# Power.net
KiCad netlist of a schematic drawn in Altium Designer
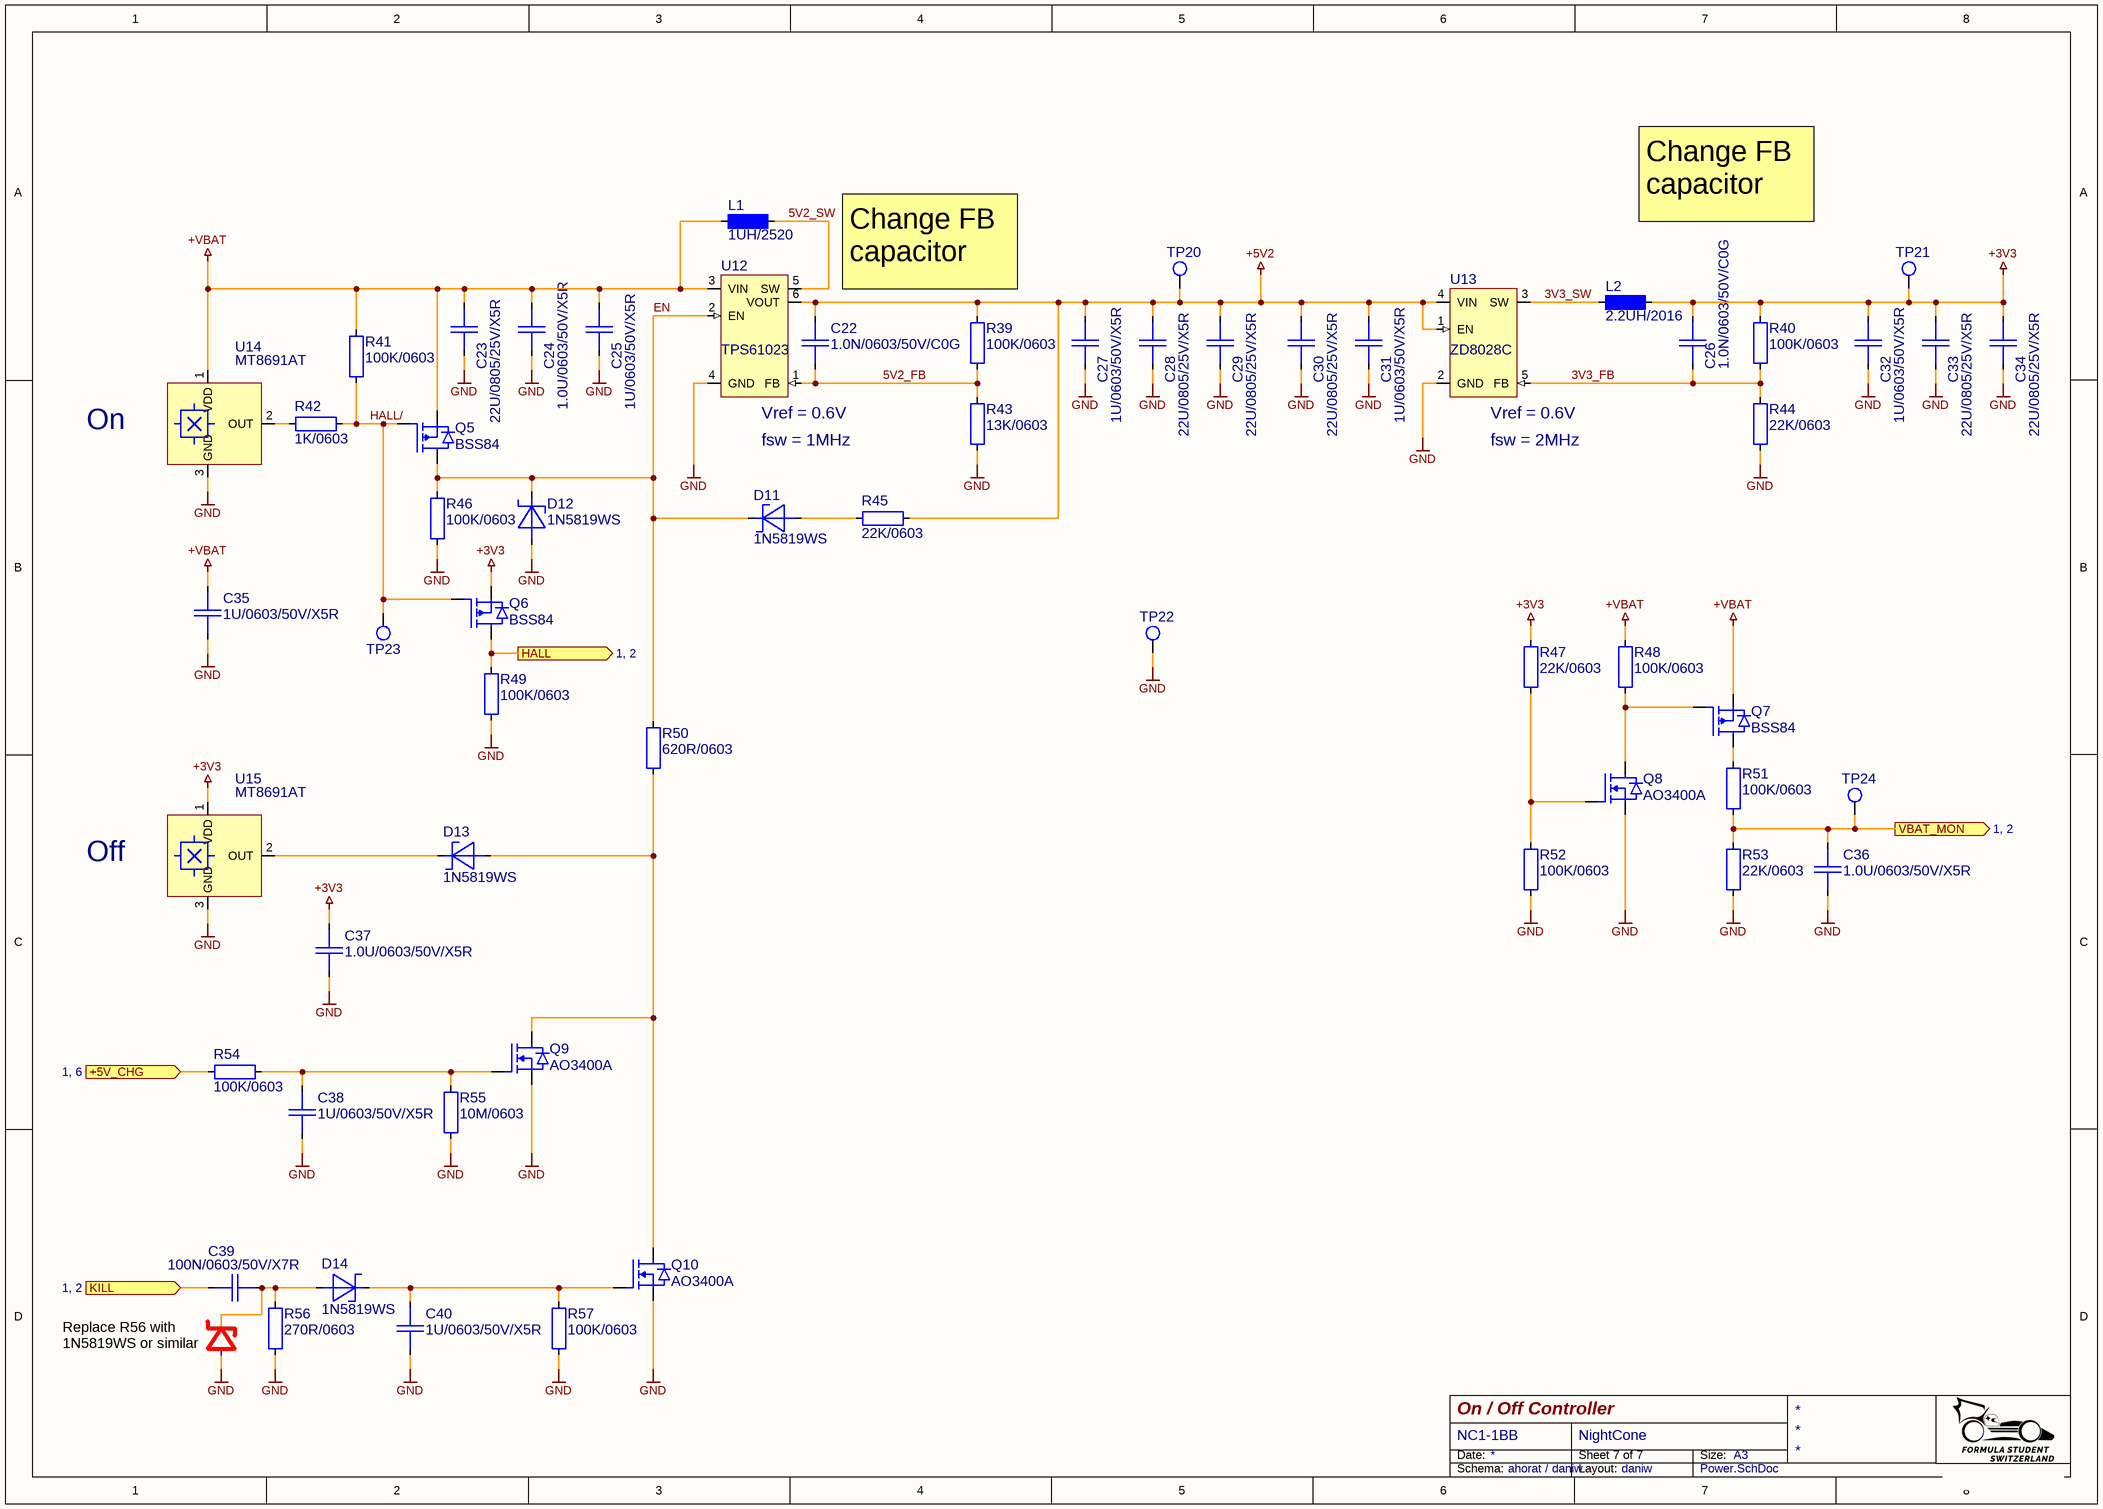
[diagram p0: Power.SchDoc]

(export (version "E")
  (design (tool "Eeschema 10.0.6"))
  (components
    (comp (ref "C22")
      (value "1.0N/0603/50V/C0G")
      (footprint "CAP0603_C0G")
      (description "CAP SM 0603 1.0nF 50V C0G")
      (fields (field (name "MANUFACTURER") "GENERIC"))
      (libsource (lib "daniw_altium_lib") (part "C"))
    )
    (comp (ref "C23")
      (value "22U/0805/25V/X5R")
      (footprint "CAP0805_X7R")
      (description "CAP SM 0805 22uF 25V X5R")
      (fields (field (name "MANUFACTURER") "GENERIC"))
      (libsource (lib "daniw_altium_lib") (part "C"))
    )
    (comp (ref "C24")
      (value "1.0U/0603/50V/X5R")
      (footprint "CAP0603_X7R")
      (description "CAP SM 0603 1.0uF 50V X5R")
      (fields (field (name "MANUFACTURER") "GENERIC"))
      (libsource (lib "daniw_altium_lib") (part "C"))
    )
    (comp (ref "C25")
      (value "1U/0603/50V/X5R")
      (footprint "CAP0603_X7R")
      (description "CAP SM 0603 1.0uF 50V X5R")
      (fields (field (name "MANUFACTURER") "GENERIC"))
      (libsource (lib "daniw_altium_lib") (part "C"))
    )
    (comp (ref "C26")
      (value "1.0N/0603/50V/C0G")
      (footprint "CAP0603_C0G")
      (description "CAP SM 0603 1.0nF 50V C0G")
      (fields (field (name "MANUFACTURER") "GENERIC"))
      (libsource (lib "daniw_altium_lib") (part "C"))
    )
    (comp (ref "C27")
      (value "1U/0603/50V/X5R")
      (footprint "CAP0603_X7R")
      (description "CAP SM 0603 1.0uF 50V X5R")
      (fields (field (name "MANUFACTURER") "GENERIC"))
      (libsource (lib "daniw_altium_lib") (part "C"))
    )
    (comp (ref "C28")
      (value "22U/0805/25V/X5R")
      (footprint "CAP0805_X7R")
      (description "CAP SM 0805 22uF 25V X5R")
      (fields (field (name "MANUFACTURER") "GENERIC"))
      (libsource (lib "daniw_altium_lib") (part "C"))
    )
    (comp (ref "C29")
      (value "22U/0805/25V/X5R")
      (footprint "CAP0805_X7R")
      (description "CAP SM 0805 22uF 25V X5R")
      (fields (field (name "MANUFACTURER") "GENERIC"))
      (libsource (lib "daniw_altium_lib") (part "C"))
    )
    (comp (ref "C30")
      (value "22U/0805/25V/X5R")
      (footprint "CAP0805_X7R")
      (description "CAP SM 0805 22uF 25V X5R")
      (fields (field (name "MANUFACTURER") "GENERIC"))
      (libsource (lib "daniw_altium_lib") (part "C"))
    )
    (comp (ref "C31")
      (value "1U/0603/50V/X5R")
      (footprint "CAP0603_X7R")
      (description "CAP SM 0603 1.0uF 50V X5R")
      (fields (field (name "MANUFACTURER") "GENERIC"))
      (libsource (lib "daniw_altium_lib") (part "C"))
    )
    (comp (ref "C32")
      (value "1U/0603/50V/X5R")
      (footprint "CAP0603_X7R")
      (description "CAP SM 0603 1.0uF 50V X5R")
      (fields (field (name "MANUFACTURER") "GENERIC"))
      (libsource (lib "daniw_altium_lib") (part "C"))
    )
    (comp (ref "C33")
      (value "22U/0805/25V/X5R")
      (footprint "CAP0805_X7R")
      (description "CAP SM 0805 22uF 25V X5R")
      (fields (field (name "MANUFACTURER") "GENERIC"))
      (libsource (lib "daniw_altium_lib") (part "C"))
    )
    (comp (ref "C34")
      (value "22U/0805/25V/X5R")
      (footprint "CAP0805_X7R")
      (description "CAP SM 0805 22uF 25V X5R")
      (fields (field (name "MANUFACTURER") "GENERIC"))
      (libsource (lib "daniw_altium_lib") (part "C"))
    )
    (comp (ref "C35")
      (value "1U/0603/50V/X5R")
      (footprint "CAP0603_X7R")
      (description "CAP SM 0603 1.0uF 50V X5R")
      (fields (field (name "MANUFACTURER") "GENERIC"))
      (libsource (lib "daniw_altium_lib") (part "C"))
    )
    (comp (ref "C36")
      (value "1.0U/0603/50V/X5R")
      (footprint "CAP0603_X7R")
      (description "CAP SM 0603 1.0uF 50V X5R")
      (fields (field (name "MANUFACTURER") "GENERIC"))
      (libsource (lib "daniw_altium_lib") (part "C"))
    )
    (comp (ref "C37")
      (value "1.0U/0603/50V/X5R")
      (footprint "CAP0603_X7R")
      (description "CAP SM 0603 1.0uF 50V X5R")
      (fields (field (name "MANUFACTURER") "GENERIC"))
      (libsource (lib "daniw_altium_lib") (part "C"))
    )
    (comp (ref "C38")
      (value "1U/0603/50V/X5R")
      (footprint "CAP0603_X7R")
      (description "CAP SM 0603 1.0uF 50V X5R")
      (fields (field (name "MANUFACTURER") "GENERIC"))
      (libsource (lib "daniw_altium_lib") (part "C"))
    )
    (comp (ref "C39")
      (value "100N/0603/50V/X7R")
      (footprint "CAP0603_X7R")
      (description "CAP SM 0603 100nF 50V X7R")
      (fields (field (name "MANUFACTURER") "GENERIC"))
      (libsource (lib "daniw_altium_lib") (part "C"))
    )
    (comp (ref "C40")
      (value "1U/0603/50V/X5R")
      (footprint "CAP0603_X7R")
      (description "CAP SM 0603 1.0uF 50V X5R")
      (fields (field (name "MANUFACTURER") "GENERIC"))
      (libsource (lib "daniw_altium_lib") (part "C"))
    )
    (comp (ref "D11")
      (value "1N5819WS")
      (footprint "SOD2513X100")
      (description "40V 600mV@1A 1A SOD-323 Schottky Barrier Diodes (SBD) ROHS")
      (fields (field (name "MANUFACTURER") "GENERIC"))
      (libsource (lib "daniw_altium_lib") (part "D_Schottky"))
    )
    (comp (ref "D12")
      (value "1N5819WS")
      (footprint "SOD2513X100")
      (description "40V 600mV@1A 1A SOD-323 Schottky Barrier Diodes (SBD) ROHS")
      (fields (field (name "MANUFACTURER") "GENERIC"))
      (libsource (lib "daniw_altium_lib") (part "D_Schottky"))
    )
    (comp (ref "D13")
      (value "1N5819WS")
      (footprint "SOD2513X100")
      (description "40V 600mV@1A 1A SOD-323 Schottky Barrier Diodes (SBD) ROHS")
      (fields (field (name "MANUFACTURER") "GENERIC"))
      (libsource (lib "daniw_altium_lib") (part "D_Schottky"))
    )
    (comp (ref "D14")
      (value "1N5819WS")
      (footprint "SOD2513X100")
      (description "40V 600mV@1A 1A SOD-323 Schottky Barrier Diodes (SBD) ROHS")
      (fields (field (name "MANUFACTURER") "GENERIC"))
      (libsource (lib "daniw_altium_lib") (part "D_Schottky"))
    )
    (comp (ref "L1")
      (value "1UH/2520")
      (footprint "INDM2520X10")
      (description "1UH 2520 Shielded Inductor SMD")
      (fields (field (name "MANUFACTURER") "GENERIC"))
      (libsource (lib "daniw_altium_lib") (part "L"))
    )
    (comp (ref "L2")
      (value "2.2UH/2016")
      (footprint "INDM2016X10")
      (description "2.2UH 2016 Shielded Inductor SMD")
      (fields (field (name "MANUFACTURER") "GENERIC"))
      (libsource (lib "daniw_altium_lib") (part "L"))
    )
    (comp (ref "Q5")
      (value "BSS84")
      (footprint "SOT2395P280X125-3-SE")
      (description "50V P-Channel MOSFET")
      (fields (field (name "MANUFACTURER") "GENERIC"))
      (libsource (lib "daniw_altium_lib") (part "MOSFET P_SOT23"))
    )
    (comp (ref "Q6")
      (value "BSS84")
      (footprint "SOT2395P280X125-3-SE")
      (description "50V P-Channel MOSFET")
      (fields (field (name "MANUFACTURER") "GENERIC"))
      (libsource (lib "daniw_altium_lib") (part "MOSFET P_SOT23"))
    )
    (comp (ref "Q7")
      (value "BSS84")
      (footprint "SOT2395P280X125-3-SE")
      (description "50V P-Channel MOSFET")
      (fields (field (name "MANUFACTURER") "GENERIC"))
      (libsource (lib "daniw_altium_lib") (part "MOSFET P_SOT23"))
    )
    (comp (ref "Q8")
      (value "AO3400A")
      (footprint "SOT2395P280X125-3-SE")
      (description "30V N-Channel MOSFET")
      (fields (field (name "MANUFACTURER") "Alpha & Omega Semiconductor"))
      (libsource (lib "daniw_altium_lib") (part "MOSFET N_SOT23"))
    )
    (comp (ref "Q9")
      (value "AO3400A")
      (footprint "SOT2395P280X125-3-SE")
      (description "30V N-Channel MOSFET")
      (fields (field (name "MANUFACTURER") "Alpha & Omega Semiconductor"))
      (libsource (lib "daniw_altium_lib") (part "MOSFET N_SOT23"))
    )
    (comp (ref "Q10")
      (value "AO3400A")
      (footprint "SOT2395P280X125-3-SE")
      (description "30V N-Channel MOSFET")
      (fields (field (name "MANUFACTURER") "Alpha & Omega Semiconductor"))
      (libsource (lib "daniw_altium_lib") (part "MOSFET N_SOT23"))
    )
    (comp (ref "R39")
      (value "100K/0603")
      (footprint "R0603-0.40-WW")
      (description "RES SM 0603 100K")
      (fields (field (name "MANUFACTURER") "GENERIC"))
      (libsource (lib "daniw_altium_lib") (part "R"))
    )
    (comp (ref "R40")
      (value "100K/0603")
      (footprint "R0603-0.40-WW")
      (description "RES SM 0603 100K")
      (fields (field (name "MANUFACTURER") "GENERIC"))
      (libsource (lib "daniw_altium_lib") (part "R"))
    )
    (comp (ref "R41")
      (value "100K/0603")
      (footprint "R0603-0.40-WW")
      (description "RES SM 0603 100K")
      (fields (field (name "MANUFACTURER") "GENERIC"))
      (libsource (lib "daniw_altium_lib") (part "R"))
    )
    (comp (ref "R42")
      (value "1K/0603")
      (footprint "R0603-0.40-WW")
      (description "RES SM 0603 1K")
      (fields (field (name "MANUFACTURER") "GENERIC"))
      (libsource (lib "daniw_altium_lib") (part "R"))
    )
    (comp (ref "R43")
      (value "13K/0603")
      (footprint "R0603-0.40-WW")
      (description "RES SM 0603 13K")
      (fields (field (name "MANUFACTURER") "GENERIC"))
      (libsource (lib "daniw_altium_lib") (part "R"))
    )
    (comp (ref "R44")
      (value "22K/0603")
      (footprint "R0603-0.40-WW")
      (description "RES SM 0603 22K")
      (fields (field (name "MANUFACTURER") "GENERIC"))
      (libsource (lib "daniw_altium_lib") (part "R"))
    )
    (comp (ref "R45")
      (value "22K/0603")
      (footprint "R0603-0.40-WW")
      (description "RES SM 0603 22K")
      (fields (field (name "MANUFACTURER") "GENERIC"))
      (libsource (lib "daniw_altium_lib") (part "R"))
    )
    (comp (ref "R46")
      (value "100K/0603")
      (footprint "R0603-0.40-WW")
      (description "RES SM 0603 100K")
      (fields (field (name "MANUFACTURER") "GENERIC"))
      (libsource (lib "daniw_altium_lib") (part "R"))
    )
    (comp (ref "R47")
      (value "22K/0603")
      (footprint "R0603-0.40-WW")
      (description "RES SM 0603 22K")
      (fields (field (name "MANUFACTURER") "GENERIC"))
      (libsource (lib "daniw_altium_lib") (part "R"))
    )
    (comp (ref "R48")
      (value "100K/0603")
      (footprint "R0603-0.40-WW")
      (description "RES SM 0603 100K")
      (fields (field (name "MANUFACTURER") "GENERIC"))
      (libsource (lib "daniw_altium_lib") (part "R"))
    )
    (comp (ref "R49")
      (value "100K/0603")
      (footprint "R0603-0.40-WW")
      (description "RES SM 0603 100K")
      (fields (field (name "MANUFACTURER") "GENERIC"))
      (libsource (lib "daniw_altium_lib") (part "R"))
    )
    (comp (ref "R50")
      (value "620R/0603")
      (footprint "R0603-0.40-WW")
      (description "RES SM 0603 620R")
      (fields (field (name "MANUFACTURER") "GENERIC"))
      (libsource (lib "daniw_altium_lib") (part "R"))
    )
    (comp (ref "R51")
      (value "100K/0603")
      (footprint "R0603-0.40-WW")
      (description "RES SM 0603 100K")
      (fields (field (name "MANUFACTURER") "GENERIC"))
      (libsource (lib "daniw_altium_lib") (part "R"))
    )
    (comp (ref "R52")
      (value "100K/0603")
      (footprint "R0603-0.40-WW")
      (description "RES SM 0603 100K")
      (fields (field (name "MANUFACTURER") "GENERIC"))
      (libsource (lib "daniw_altium_lib") (part "R"))
    )
    (comp (ref "R53")
      (value "22K/0603")
      (footprint "R0603-0.40-WW")
      (description "RES SM 0603 22K")
      (fields (field (name "MANUFACTURER") "GENERIC"))
      (libsource (lib "daniw_altium_lib") (part "R"))
    )
    (comp (ref "R54")
      (value "100K/0603")
      (footprint "R0603-0.40-WW")
      (description "RES SM 0603 100K")
      (fields (field (name "MANUFACTURER") "GENERIC"))
      (libsource (lib "daniw_altium_lib") (part "R"))
    )
    (comp (ref "R55")
      (value "10M/0603")
      (footprint "R0603-0.40-WW")
      (description "RES SM 0603 10M")
      (fields (field (name "MANUFACTURER") "GENERIC"))
      (libsource (lib "daniw_altium_lib") (part "R"))
    )
    (comp (ref "R56")
      (value "270R/0603")
      (footprint "R0603-0.40-WW")
      (description "RES SM 0603 270R")
      (fields (field (name "MANUFACTURER") "GENERIC"))
      (libsource (lib "daniw_altium_lib") (part "R"))
    )
    (comp (ref "R57")
      (value "100K/0603")
      (footprint "R0603-0.40-WW")
      (description "RES SM 0603 100K")
      (fields (field (name "MANUFACTURER") "GENERIC"))
      (libsource (lib "daniw_altium_lib") (part "R"))
    )
    (comp (ref "TP20")
      (value "TP_THD_1.5/0.8")
      (footprint "TP_THD_1.5/0.8")
      (description "THT Test Point 1.5/0.8mm")
      (fields (field (name "MANUFACTURER") "NONE"))
      (libsource (lib "daniw_altium_lib") (part "Testpoint"))
    )
    (comp (ref "TP21")
      (value "TP_THD_1.5/0.8")
      (footprint "TP_THD_1.5/0.8")
      (description "THT Test Point 1.5/0.8mm")
      (fields (field (name "MANUFACTURER") "NONE"))
      (libsource (lib "daniw_altium_lib") (part "Testpoint"))
    )
    (comp (ref "TP22")
      (value "TP_THD_1.5/0.8")
      (footprint "TP_THD_1.5/0.8")
      (description "THT Test Point 1.5/0.8mm")
      (fields (field (name "MANUFACTURER") "NONE"))
      (libsource (lib "daniw_altium_lib") (part "Testpoint"))
    )
    (comp (ref "TP23")
      (value "TP_THD_1.5/0.8")
      (footprint "TP_THD_1.5/0.8")
      (description "THT Test Point 1.5/0.8mm")
      (fields (field (name "MANUFACTURER") "NONE"))
      (libsource (lib "daniw_altium_lib") (part "Testpoint"))
    )
    (comp (ref "TP24")
      (value "TP_THD_1.5/0.8")
      (footprint "TP_THD_1.5/0.8")
      (description "THT Test Point 1.5/0.8mm")
      (fields (field (name "MANUFACTURER") "NONE"))
      (libsource (lib "daniw_altium_lib") (part "Testpoint"))
    )
    (comp (ref "U12")
      (value "TPS61023")
      (footprint "SOT50P160X60-6-SE")
      (description "3.7-A Boost Converter with 0.5-V Ultra-low Input Voltage")
      (fields (field (name "MANUFACTURER") "Texas Instruments"))
      (libsource (lib "daniw_altium_lib") (part "TPS61023"))
    )
    (comp (ref "U13")
      (value "ZD8028C")
      (footprint "SOT2395P280X125-5-SW")
      (description "1.5A 2MHz 5.5V Synchronous Buck Converter")
      (fields (field (name "MANUFACTURER") "Zetta"))
      (libsource (lib "daniw_altium_lib") (part "ZD8028C"))
    )
    (comp (ref "U14")
      (value "MT8691AT")
      (footprint "SOT2395P280X125-3-SE")
      (description "MT8691AT Uni-polar, Nano Power Hall-Effect Switch IC")
      (fields (field (name "MANUFACTURER") "Magn Tek"))
      (libsource (lib "daniw_altium_lib") (part "UHE4913"))
    )
    (comp (ref "U15")
      (value "MT8691AT")
      (footprint "SOT2395P280X125-3-SE")
      (description "MT8691AT Uni-polar, Nano Power Hall-Effect Switch IC")
      (fields (field (name "MANUFACTURER") "Magn Tek"))
      (libsource (lib "daniw_altium_lib") (part "UHE4913"))
    )
  )
  (nets
    (net (code "1") (name "+3V3") (class "Default")
      (node (ref "C26") (pin "1") (pinfunction "1_1") (pintype "passive"))
      (node (ref "C32") (pin "2") (pinfunction "2_2") (pintype "passive"))
      (node (ref "C33") (pin "1") (pinfunction "1_1") (pintype "passive"))
      (node (ref "C34") (pin "1") (pinfunction "1_1") (pintype "passive"))
      (node (ref "C37") (pin "1") (pinfunction "1_1") (pintype "passive"))
      (node (ref "L2") (pin "2") (pinfunction "2_2") (pintype "passive"))
      (node (ref "Q6") (pin "2") (pinfunction "SOURCE_2") (pintype "passive"))
      (node (ref "R40") (pin "1") (pinfunction "1_1") (pintype "passive"))
      (node (ref "R47") (pin "1") (pinfunction "1_1") (pintype "passive"))
      (node (ref "TP21") (pin "1") (pinfunction "1_1") (pintype "passive"))
      (node (ref "U15") (pin "1") (pinfunction "VDD_1") (pintype "passive"))
    )
    (net (code "2") (name "+5V2") (class "Default")
      (node (ref "C22") (pin "1") (pinfunction "1_1") (pintype "passive"))
      (node (ref "C27") (pin "2") (pinfunction "2_2") (pintype "passive"))
      (node (ref "C28") (pin "1") (pinfunction "1_1") (pintype "passive"))
      (node (ref "C29") (pin "1") (pinfunction "1_1") (pintype "passive"))
      (node (ref "C30") (pin "1") (pinfunction "1_1") (pintype "passive"))
      (node (ref "C31") (pin "2") (pinfunction "2_2") (pintype "passive"))
      (node (ref "R39") (pin "1") (pinfunction "1_1") (pintype "passive"))
      (node (ref "R45") (pin "2") (pinfunction "2_2") (pintype "passive"))
      (node (ref "TP20") (pin "1") (pinfunction "1_1") (pintype "passive"))
      (node (ref "U12") (pin "6") (pinfunction "VOUT_6") (pintype "passive"))
      (node (ref "U13") (pin "1") (pinfunction "EN_1") (pintype "input"))
      (node (ref "U13") (pin "4") (pinfunction "VIN_4") (pintype "passive"))
    )
    (net (code "3") (name "+VBAT") (class "Default")
      (node (ref "C23") (pin "1") (pinfunction "1_1") (pintype "passive"))
      (node (ref "C24") (pin "2") (pinfunction "2_2") (pintype "passive"))
      (node (ref "C25") (pin "2") (pinfunction "2_2") (pintype "passive"))
      (node (ref "C35") (pin "1") (pinfunction "1_1") (pintype "passive"))
      (node (ref "L1") (pin "1") (pinfunction "1_1") (pintype "passive"))
      (node (ref "Q5") (pin "2") (pinfunction "SOURCE_2") (pintype "passive"))
      (node (ref "Q7") (pin "2") (pinfunction "SOURCE_2") (pintype "passive"))
      (node (ref "R41") (pin "1") (pinfunction "1_1") (pintype "passive"))
      (node (ref "R48") (pin "1") (pinfunction "1_1") (pintype "passive"))
      (node (ref "U12") (pin "3") (pinfunction "VIN_3") (pintype "passive"))
      (node (ref "U14") (pin "1") (pinfunction "VDD_1") (pintype "passive"))
    )
    (net (code "4") (name "/+5V_CHG") (class "Default")
      (node (ref "R54") (pin "1") (pinfunction "1_1") (pintype "passive"))
    )
    (net (code "5") (name "/3V3_FB") (class "Default")
      (node (ref "C26") (pin "2") (pinfunction "2_2") (pintype "passive"))
      (node (ref "R40") (pin "2") (pinfunction "2_2") (pintype "passive"))
      (node (ref "R44") (pin "1") (pinfunction "1_1") (pintype "passive"))
      (node (ref "U13") (pin "5") (pinfunction "FB_5") (pintype "input"))
    )
    (net (code "6") (name "/3V3_SW") (class "Default")
      (node (ref "L2") (pin "1") (pinfunction "1_1") (pintype "passive"))
      (node (ref "U13") (pin "3") (pinfunction "SW_3") (pintype "passive"))
    )
    (net (code "7") (name "/5V2_FB") (class "Default")
      (node (ref "C22") (pin "2") (pinfunction "2_2") (pintype "passive"))
      (node (ref "R39") (pin "2") (pinfunction "2_2") (pintype "passive"))
      (node (ref "R43") (pin "2") (pinfunction "2_2") (pintype "passive"))
      (node (ref "U12") (pin "1") (pinfunction "FB_1") (pintype "input"))
    )
    (net (code "8") (name "/5V2_SW") (class "Default")
      (node (ref "L1") (pin "2") (pinfunction "2_2") (pintype "passive"))
      (node (ref "U12") (pin "5") (pinfunction "SW_5") (pintype "passive"))
    )
    (net (code "9") (name "/EN") (class "Default")
      (node (ref "D11") (pin "1") (pinfunction "1_1") (pintype "passive"))
      (node (ref "D12") (pin "1") (pinfunction "1_1") (pintype "passive"))
      (node (ref "Q5") (pin "3") (pinfunction "DRAIN_3") (pintype "passive"))
      (node (ref "R46") (pin "1") (pinfunction "1_1") (pintype "passive"))
      (node (ref "R50") (pin "1") (pinfunction "1_1") (pintype "passive"))
      (node (ref "U12") (pin "2") (pinfunction "EN_2") (pintype "input"))
    )
    (net (code "10") (name "/HALL") (class "Default")
      (node (ref "Q6") (pin "3") (pinfunction "DRAIN_3") (pintype "passive"))
      (node (ref "R49") (pin "1") (pinfunction "1_1") (pintype "passive"))
    )
    (net (code "11") (name "/HALL{slash}") (class "Default")
      (node (ref "Q5") (pin "1") (pinfunction "GATE_1") (pintype "passive"))
      (node (ref "Q6") (pin "1") (pinfunction "GATE_1") (pintype "passive"))
      (node (ref "R41") (pin "2") (pinfunction "2_2") (pintype "passive"))
      (node (ref "R42") (pin "2") (pinfunction "2_2") (pintype "passive"))
      (node (ref "TP23") (pin "1") (pinfunction "1_1") (pintype "passive"))
    )
    (net (code "12") (name "/KILL") (class "Default")
      (node (ref "C39") (pin "1") (pinfunction "1_1") (pintype "passive"))
    )
    (net (code "13") (name "/VBAT_MON") (class "Default")
      (node (ref "C36") (pin "1") (pinfunction "1_1") (pintype "passive"))
      (node (ref "R51") (pin "2") (pinfunction "2_2") (pintype "passive"))
      (node (ref "R53") (pin "1") (pinfunction "1_1") (pintype "passive"))
      (node (ref "TP24") (pin "1") (pinfunction "1_1") (pintype "passive"))
    )
    (net (code "14") (name "GND") (class "Default")
      (node (ref "C23") (pin "2") (pinfunction "2_2") (pintype "passive"))
      (node (ref "C24") (pin "1") (pinfunction "1_1") (pintype "passive"))
      (node (ref "C25") (pin "1") (pinfunction "1_1") (pintype "passive"))
      (node (ref "C27") (pin "1") (pinfunction "1_1") (pintype "passive"))
      (node (ref "C28") (pin "2") (pinfunction "2_2") (pintype "passive"))
      (node (ref "C29") (pin "2") (pinfunction "2_2") (pintype "passive"))
      (node (ref "C30") (pin "2") (pinfunction "2_2") (pintype "passive"))
      (node (ref "C31") (pin "1") (pinfunction "1_1") (pintype "passive"))
      (node (ref "C32") (pin "1") (pinfunction "1_1") (pintype "passive"))
      (node (ref "C33") (pin "2") (pinfunction "2_2") (pintype "passive"))
      (node (ref "C34") (pin "2") (pinfunction "2_2") (pintype "passive"))
      (node (ref "C35") (pin "2") (pinfunction "2_2") (pintype "passive"))
      (node (ref "C36") (pin "2") (pinfunction "2_2") (pintype "passive"))
      (node (ref "C37") (pin "2") (pinfunction "2_2") (pintype "passive"))
      (node (ref "C38") (pin "2") (pinfunction "2_2") (pintype "passive"))
      (node (ref "C40") (pin "2") (pinfunction "2_2") (pintype "passive"))
      (node (ref "D12") (pin "2") (pinfunction "2_2") (pintype "passive"))
      (node (ref "Q10") (pin "2") (pinfunction "SOURCE_2") (pintype "passive"))
      (node (ref "Q8") (pin "2") (pinfunction "SOURCE_2") (pintype "passive"))
      (node (ref "Q9") (pin "2") (pinfunction "SOURCE_2") (pintype "passive"))
      (node (ref "R43") (pin "1") (pinfunction "1_1") (pintype "passive"))
      (node (ref "R44") (pin "2") (pinfunction "2_2") (pintype "passive"))
      (node (ref "R46") (pin "2") (pinfunction "2_2") (pintype "passive"))
      (node (ref "R49") (pin "2") (pinfunction "2_2") (pintype "passive"))
      (node (ref "R52") (pin "2") (pinfunction "2_2") (pintype "passive"))
      (node (ref "R53") (pin "2") (pinfunction "2_2") (pintype "passive"))
      (node (ref "R55") (pin "2") (pinfunction "2_2") (pintype "passive"))
      (node (ref "R56") (pin "2") (pinfunction "2_2") (pintype "passive"))
      (node (ref "R57") (pin "2") (pinfunction "2_2") (pintype "passive"))
      (node (ref "TP22") (pin "1") (pinfunction "1_1") (pintype "passive"))
      (node (ref "U12") (pin "4") (pinfunction "GND_4") (pintype "passive"))
      (node (ref "U13") (pin "2") (pinfunction "GND_2") (pintype "passive"))
      (node (ref "U14") (pin "3") (pinfunction "GND_3") (pintype "passive"))
      (node (ref "U15") (pin "3") (pinfunction "GND_3") (pintype "passive"))
    )
    (net (code "15") (name "Net-(C39-Pad2)") (class "Default")
      (node (ref "C39") (pin "2") (pinfunction "2_2") (pintype "passive"))
      (node (ref "D14") (pin "2") (pinfunction "2_2") (pintype "passive"))
      (node (ref "R56") (pin "1") (pinfunction "1_1") (pintype "passive"))
    )
    (net (code "16") (name "Net-(D11-Pad2)") (class "Default")
      (node (ref "D11") (pin "2") (pinfunction "2_2") (pintype "passive"))
      (node (ref "R45") (pin "1") (pinfunction "1_1") (pintype "passive"))
    )
    (net (code "17") (name "Net-(Q7-DRAIN)") (class "Default")
      (node (ref "Q7") (pin "3") (pinfunction "DRAIN_3") (pintype "passive"))
      (node (ref "R51") (pin "1") (pinfunction "1_1") (pintype "passive"))
    )
    (net (code "18") (name "Net-(Q7-GATE)") (class "Default")
      (node (ref "Q7") (pin "1") (pinfunction "GATE_1") (pintype "passive"))
      (node (ref "Q8") (pin "3") (pinfunction "DRAIN_3") (pintype "passive"))
      (node (ref "R48") (pin "2") (pinfunction "2_2") (pintype "passive"))
    )
    (net (code "19") (name "Net-(Q8-GATE)") (class "Default")
      (node (ref "Q8") (pin "1") (pinfunction "GATE_1") (pintype "passive"))
      (node (ref "R47") (pin "2") (pinfunction "2_2") (pintype "passive"))
      (node (ref "R52") (pin "1") (pinfunction "1_1") (pintype "passive"))
    )
    (net (code "20") (name "Net-(Q9-GATE)") (class "Default")
      (node (ref "C38") (pin "1") (pinfunction "1_1") (pintype "passive"))
      (node (ref "Q9") (pin "1") (pinfunction "GATE_1") (pintype "passive"))
      (node (ref "R54") (pin "2") (pinfunction "2_2") (pintype "passive"))
      (node (ref "R55") (pin "1") (pinfunction "1_1") (pintype "passive"))
    )
    (net (code "21") (name "Net-(Q10-DRAIN)") (class "Default")
      (node (ref "D13") (pin "2") (pinfunction "2_2") (pintype "passive"))
      (node (ref "Q10") (pin "3") (pinfunction "DRAIN_3") (pintype "passive"))
      (node (ref "Q9") (pin "3") (pinfunction "DRAIN_3") (pintype "passive"))
      (node (ref "R50") (pin "2") (pinfunction "2_2") (pintype "passive"))
    )
    (net (code "22") (name "Net-(Q10-GATE)") (class "Default")
      (node (ref "C40") (pin "1") (pinfunction "1_1") (pintype "passive"))
      (node (ref "D14") (pin "1") (pinfunction "1_1") (pintype "passive"))
      (node (ref "Q10") (pin "1") (pinfunction "GATE_1") (pintype "passive"))
      (node (ref "R57") (pin "1") (pinfunction "1_1") (pintype "passive"))
    )
    (net (code "23") (name "Net-(U14-OUT)") (class "Default")
      (node (ref "R42") (pin "1") (pinfunction "1_1") (pintype "passive"))
      (node (ref "U14") (pin "2") (pinfunction "OUT_2") (pintype "open_collector"))
    )
    (net (code "24") (name "Net-(U15-OUT)") (class "Default")
      (node (ref "D13") (pin "1") (pinfunction "1_1") (pintype "passive"))
      (node (ref "U15") (pin "2") (pinfunction "OUT_2") (pintype "open_collector"))
    )
  )
)
